# PCB1M1A1.net
KiCad netlist of a schematic drawn in EAGLE
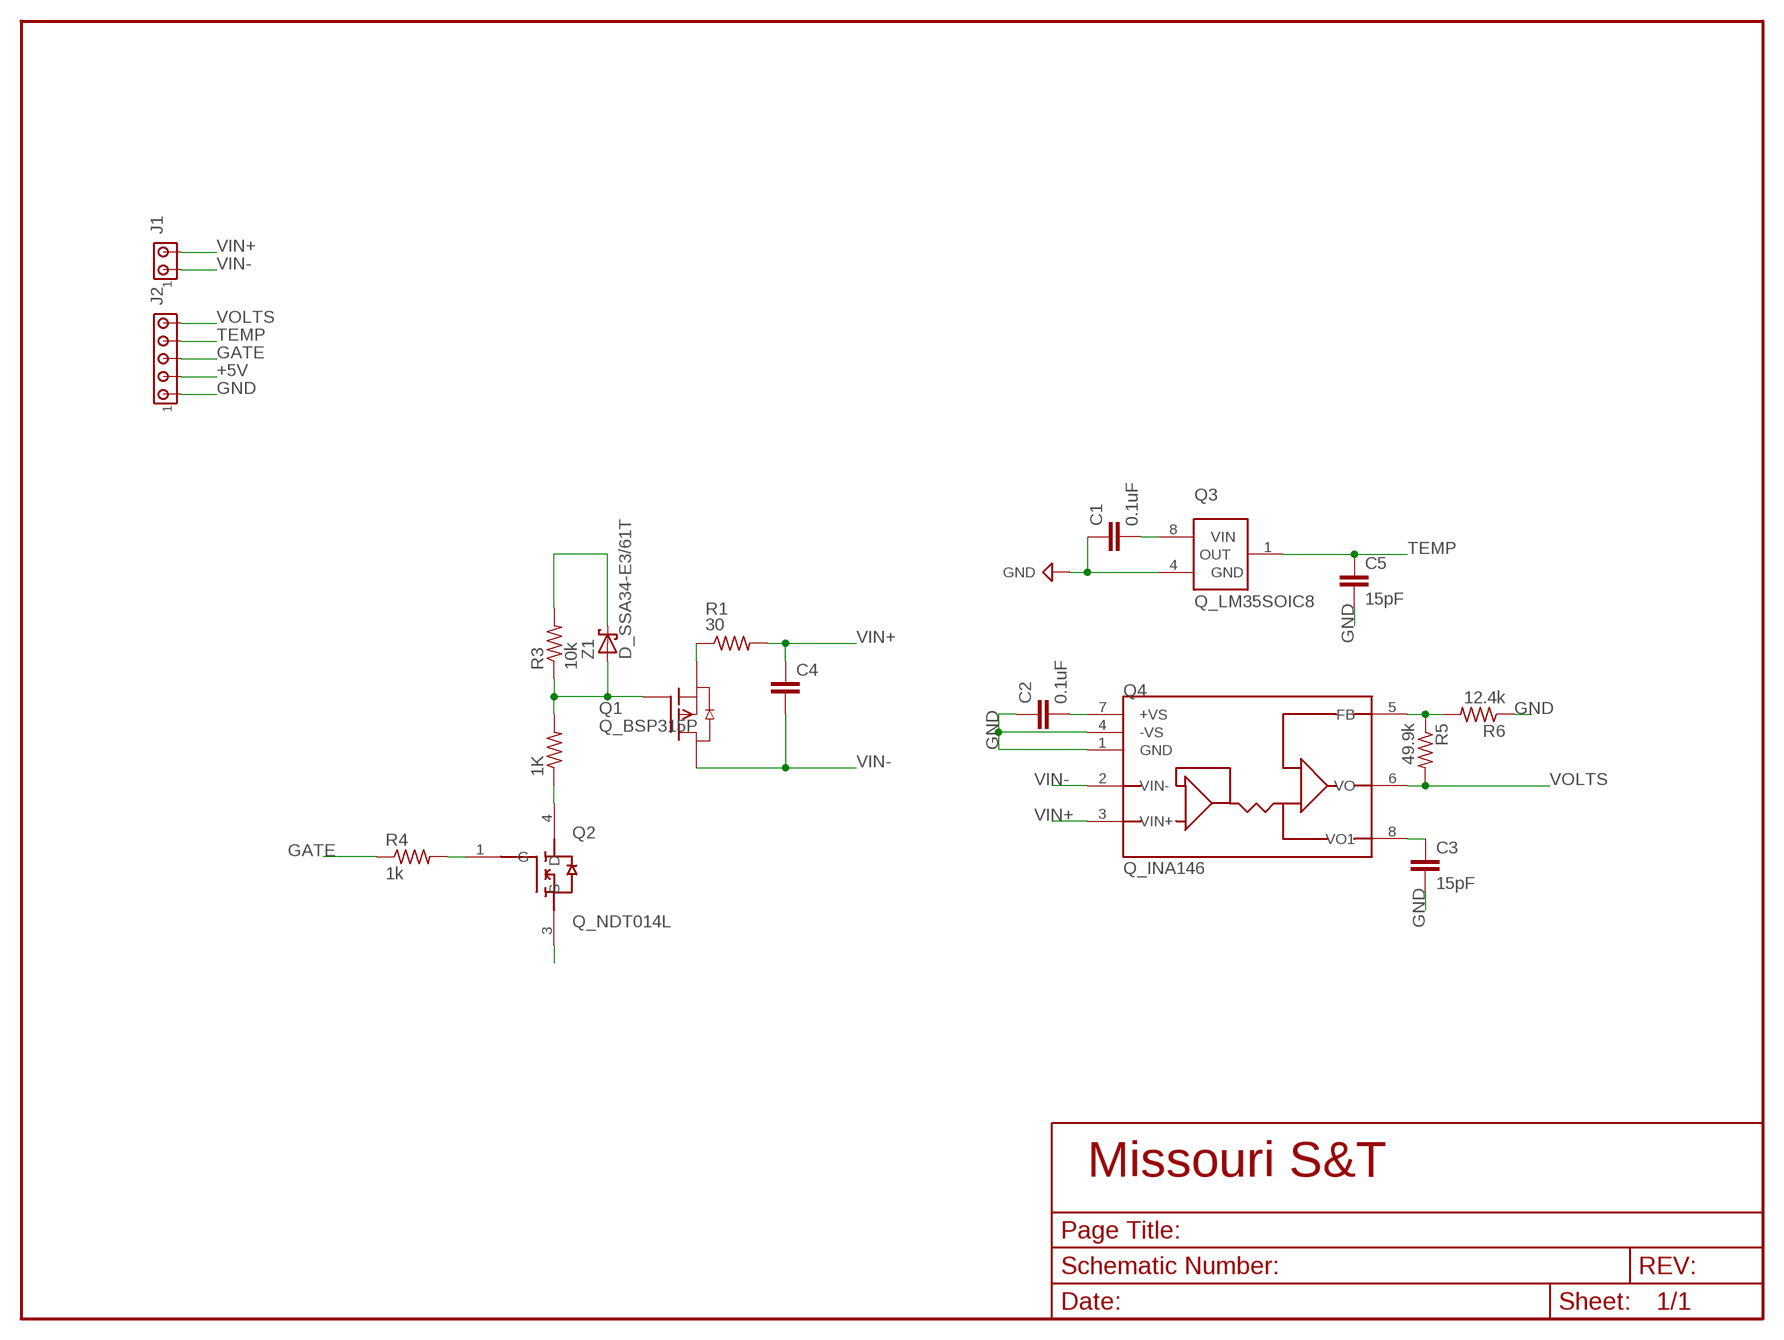
[diagram p0: schematic, sheet 1]

(export (version "E")
  (design (tool "Eeschema 10.0.6"))
  (components
    (comp (ref "1K")
      (value "R_RES_1206")
      (footprint "eagle-import:R_1206")
      (libsource (lib "eagle-import") (part "R_RES_1206"))
    )
    (comp (ref "C1")
      (value "0.1uF")
      (footprint "eagle-import:C_1206")
      (libsource (lib "eagle-import") (part "C_CAP_1206"))
    )
    (comp (ref "C2")
      (value "0.1uF")
      (footprint "eagle-import:C_1206")
      (libsource (lib "eagle-import") (part "C_CAP_1206"))
    )
    (comp (ref "C3")
      (value "15pF")
      (footprint "eagle-import:C_1206")
      (libsource (lib "eagle-import") (part "C_CAP_1206"))
    )
    (comp (ref "C4")
      (value "C_CAP_1206")
      (footprint "eagle-import:C_1206")
      (libsource (lib "eagle-import") (part "C_CAP_1206"))
    )
    (comp (ref "C5")
      (value "15pF")
      (footprint "eagle-import:C_1206")
      (libsource (lib "eagle-import") (part "C_CAP_1206"))
    )
    (comp (ref "J1")
      (value "J_MTA2P_100")
      (footprint "eagle-import:J_MTA100_2P")
      (libsource (lib "eagle-import") (part "J_MTA2P_100"))
    )
    (comp (ref "J2")
      (value "J_MTA5P_100")
      (footprint "eagle-import:J_MTA100_5P")
      (libsource (lib "eagle-import") (part "J_MTA5P_100"))
    )
    (comp (ref "Q1")
      (value "Q_BSP315P")
      (footprint "eagle-import:SOT-223")
      (libsource (lib "eagle-import") (part "Q_BSP315P"))
    )
    (comp (ref "Q2")
      (value "Q_NDT014L")
      (footprint "eagle-import:SOT-223")
      (libsource (lib "eagle-import") (part "Q_NDT014L"))
    )
    (comp (ref "Q3")
      (value "Q_LM35SOIC8")
      (footprint "eagle-import:SOIC8")
      (libsource (lib "eagle-import") (part "Q_LM35SOIC8"))
    )
    (comp (ref "Q4")
      (value "Q_INA146")
      (footprint "eagle-import:SOIC8")
      (libsource (lib "eagle-import") (part "Q_INA146"))
    )
    (comp (ref "R1")
      (value "30")
      (footprint "eagle-import:R_2512")
      (libsource (lib "eagle-import") (part "R_2512"))
    )
    (comp (ref "R3")
      (value "10k")
      (footprint "eagle-import:R_1206")
      (libsource (lib "eagle-import") (part "R_RES_1206"))
    )
    (comp (ref "R4")
      (value "1k")
      (footprint "eagle-import:R_1206")
      (libsource (lib "eagle-import") (part "R_RES_1206"))
    )
    (comp (ref "R5")
      (value "49.9k")
      (footprint "eagle-import:R_1206")
      (libsource (lib "eagle-import") (part "R_RES_1206"))
    )
    (comp (ref "R6")
      (value "12.4k")
      (footprint "eagle-import:R_1206")
      (libsource (lib "eagle-import") (part "R_RES_1206"))
    )
    (comp (ref "Z1")
      (value "D_SSA34-E3/61T")
      (footprint "eagle-import:D_DO214AC")
      (libsource (lib "eagle-import") (part "D_SSA34-E3/61T"))
    )
  )
  (nets
    (net (code "1") (name "/+5V") (class "Default")
      (node (ref "C1") (pin "2") (pinfunction "2_2") (pintype "passive"))
      (node (ref "C2") (pin "2") (pinfunction "2_2") (pintype "passive"))
      (node (ref "J2") (pin "2") (pinfunction "2_2") (pintype "passive"))
      (node (ref "Q3") (pin "8") (pinfunction "VIN_8") (pintype "bidirectional"))
      (node (ref "Q4") (pin "7") (pinfunction "+VS_7") (pintype "bidirectional"))
    )
    (net (code "2") (name "/GATE") (class "Default")
      (node (ref "J2") (pin "3") (pinfunction "3_3") (pintype "passive"))
      (node (ref "R4") (pin "1") (pinfunction "1_1") (pintype "passive"))
    )
    (net (code "3") (name "/TEMP") (class "Default")
      (node (ref "C5") (pin "1") (pinfunction "1_1") (pintype "passive"))
      (node (ref "J2") (pin "4") (pinfunction "4_4") (pintype "passive"))
      (node (ref "Q3") (pin "1") (pinfunction "OUT_1") (pintype "bidirectional"))
    )
    (net (code "4") (name "/VIN+") (class "Default")
      (node (ref "C4") (pin "1") (pinfunction "1_1") (pintype "passive"))
      (node (ref "J1") (pin "2") (pinfunction "2_2") (pintype "passive"))
      (node (ref "Q4") (pin "3") (pinfunction "VIN+_3") (pintype "bidirectional"))
      (node (ref "R1") (pin "P$2") (pinfunction "2_P$2") (pintype "passive"))
    )
    (net (code "5") (name "/VIN-") (class "Default")
      (node (ref "C4") (pin "2") (pinfunction "2_2") (pintype "passive"))
      (node (ref "J1") (pin "1") (pinfunction "1_1") (pintype "passive"))
      (node (ref "Q1") (pin "3") (pinfunction "D_3") (pintype "passive"))
      (node (ref "Q4") (pin "2") (pinfunction "VIN-_2") (pintype "bidirectional"))
    )
    (net (code "6") (name "/VOLTS") (class "Default")
      (node (ref "J2") (pin "5") (pinfunction "5_5") (pintype "passive"))
      (node (ref "Q4") (pin "6") (pinfunction "VO_6") (pintype "bidirectional"))
      (node (ref "R5") (pin "2") (pinfunction "2_2") (pintype "passive"))
    )
    (net (code "7") (name "Net-(Q1-G)") (class "Default")
      (node (ref "1K") (pin "2") (pinfunction "2_2") (pintype "passive"))
      (node (ref "Q1") (pin "1") (pinfunction "G_1") (pintype "passive"))
      (node (ref "R3") (pin "1") (pinfunction "1_1") (pintype "passive"))
      (node (ref "Z1") (pin "A") (pinfunction "A_A") (pintype "passive"))
    )
    (net (code "8") (name "Net-(Q1-S)") (class "Default")
      (node (ref "Q1") (pin "4") (pinfunction "S_4") (pintype "passive"))
      (node (ref "R1") (pin "P$1") (pinfunction "1_P$1") (pintype "passive"))
    )
    (net (code "9") (name "Net-(Q2-D)") (class "Default")
      (node (ref "1K") (pin "1") (pinfunction "1_1") (pintype "passive"))
      (node (ref "Q2") (pin "4") (pinfunction "D_4") (pintype "bidirectional"))
    )
    (net (code "10") (name "Net-(Q2-G)") (class "Default")
      (node (ref "Q2") (pin "1") (pinfunction "G_1") (pintype "bidirectional"))
      (node (ref "R4") (pin "2") (pinfunction "2_2") (pintype "passive"))
    )
    (net (code "11") (name "Net-(Q4-FB)") (class "Default")
      (node (ref "Q4") (pin "5") (pinfunction "FB_5") (pintype "bidirectional"))
      (node (ref "R5") (pin "1") (pinfunction "1_1") (pintype "passive"))
      (node (ref "R6") (pin "2") (pinfunction "2_2") (pintype "passive"))
    )
    (net (code "12") (name "Net-(Q4-VO1)") (class "Default")
      (node (ref "C3") (pin "1") (pinfunction "1_1") (pintype "passive"))
      (node (ref "Q4") (pin "8") (pinfunction "VO1_8") (pintype "bidirectional"))
    )
    (net (code "13") (name "Net-(R3-Pad2)") (class "Default")
      (node (ref "R3") (pin "2") (pinfunction "2_2") (pintype "passive"))
      (node (ref "Z1") (pin "C") (pinfunction "C_C") (pintype "passive"))
    )
    (net (code "14") (name "SUP_GND") (class "Default")
      (node (ref "C1") (pin "1") (pinfunction "1_1") (pintype "passive"))
      (node (ref "C2") (pin "1") (pinfunction "1_1") (pintype "passive"))
      (node (ref "C3") (pin "2") (pinfunction "2_2") (pintype "passive"))
      (node (ref "C5") (pin "2") (pinfunction "2_2") (pintype "passive"))
      (node (ref "J2") (pin "1") (pinfunction "1_1") (pintype "passive"))
      (node (ref "Q2") (pin "3") (pinfunction "S_3") (pintype "bidirectional"))
      (node (ref "Q3") (pin "4") (pinfunction "GND_4") (pintype "bidirectional"))
      (node (ref "Q4") (pin "1") (pinfunction "GND_1") (pintype "bidirectional"))
      (node (ref "Q4") (pin "4") (pinfunction "-VS_4") (pintype "bidirectional"))
      (node (ref "R6") (pin "1") (pinfunction "1_1") (pintype "passive"))
    )
  )
)
